# nandboard-pcb_rev_d.net
KiCad netlist of a schematic drawn in EAGLE
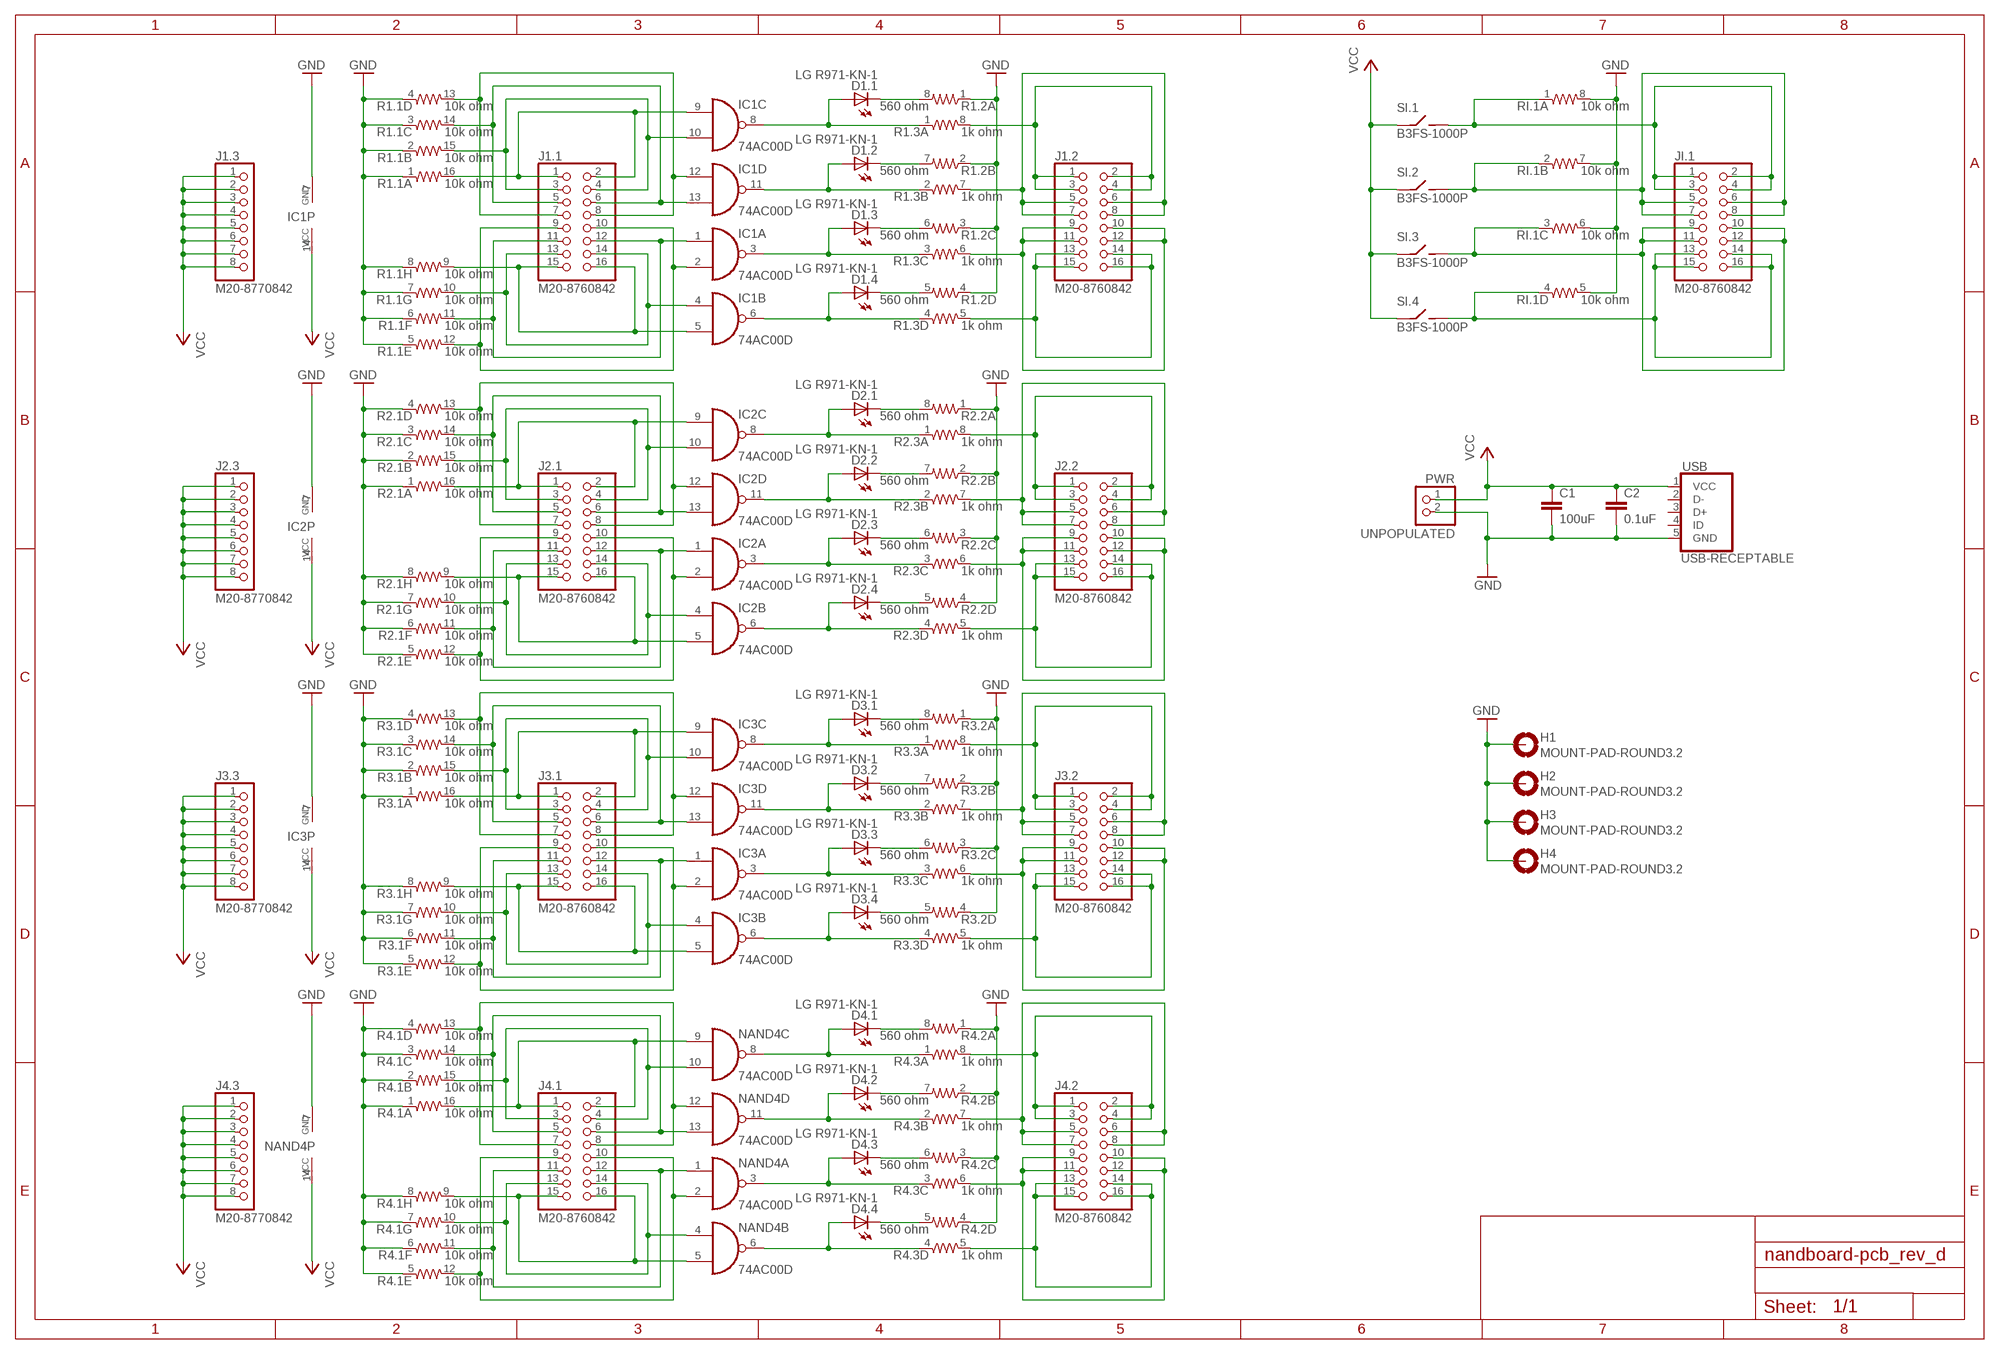
[diagram p0: schematic, sheet 1]

(export (version "E")
  (design (tool "Eeschema 10.0.6"))
  (components
    (comp (ref "C1")
      (value "100uF")
      (footprint "eagle-import:C1210")
      (libsource (lib "eagle-import") (part "C-EUC1210"))
    )
    (comp (ref "C2")
      (value "0.1uF")
      (footprint "eagle-import:C0805")
      (libsource (lib "eagle-import") (part "C-EUC0805"))
    )
    (comp (ref "D1.1")
      (value "LG R971-KN-1")
      (footprint "eagle-import:CHIPLED_0805")
      (libsource (lib "eagle-import") (part "LEDCHIPLED_0805"))
    )
    (comp (ref "D1.2")
      (value "LG R971-KN-1")
      (footprint "eagle-import:CHIPLED_0805")
      (libsource (lib "eagle-import") (part "LEDCHIPLED_0805"))
    )
    (comp (ref "D1.3")
      (value "LG R971-KN-1")
      (footprint "eagle-import:CHIPLED_0805")
      (libsource (lib "eagle-import") (part "LEDCHIPLED_0805"))
    )
    (comp (ref "D1.4")
      (value "LG R971-KN-1")
      (footprint "eagle-import:CHIPLED_0805")
      (libsource (lib "eagle-import") (part "LEDCHIPLED_0805"))
    )
    (comp (ref "D2.1")
      (value "LG R971-KN-1")
      (footprint "eagle-import:CHIPLED_0805")
      (libsource (lib "eagle-import") (part "LEDCHIPLED_0805"))
    )
    (comp (ref "D2.2")
      (value "LG R971-KN-1")
      (footprint "eagle-import:CHIPLED_0805")
      (libsource (lib "eagle-import") (part "LEDCHIPLED_0805"))
    )
    (comp (ref "D2.3")
      (value "LG R971-KN-1")
      (footprint "eagle-import:CHIPLED_0805")
      (libsource (lib "eagle-import") (part "LEDCHIPLED_0805"))
    )
    (comp (ref "D2.4")
      (value "LG R971-KN-1")
      (footprint "eagle-import:CHIPLED_0805")
      (libsource (lib "eagle-import") (part "LEDCHIPLED_0805"))
    )
    (comp (ref "D3.1")
      (value "LG R971-KN-1")
      (footprint "eagle-import:CHIPLED_0805")
      (libsource (lib "eagle-import") (part "LEDCHIPLED_0805"))
    )
    (comp (ref "D3.2")
      (value "LG R971-KN-1")
      (footprint "eagle-import:CHIPLED_0805")
      (libsource (lib "eagle-import") (part "LEDCHIPLED_0805"))
    )
    (comp (ref "D3.3")
      (value "LG R971-KN-1")
      (footprint "eagle-import:CHIPLED_0805")
      (libsource (lib "eagle-import") (part "LEDCHIPLED_0805"))
    )
    (comp (ref "D3.4")
      (value "LG R971-KN-1")
      (footprint "eagle-import:CHIPLED_0805")
      (libsource (lib "eagle-import") (part "LEDCHIPLED_0805"))
    )
    (comp (ref "D4.1")
      (value "LG R971-KN-1")
      (footprint "eagle-import:CHIPLED_0805")
      (libsource (lib "eagle-import") (part "LEDCHIPLED_0805"))
    )
    (comp (ref "D4.2")
      (value "LG R971-KN-1")
      (footprint "eagle-import:CHIPLED_0805")
      (libsource (lib "eagle-import") (part "LEDCHIPLED_0805"))
    )
    (comp (ref "D4.3")
      (value "LG R971-KN-1")
      (footprint "eagle-import:CHIPLED_0805")
      (libsource (lib "eagle-import") (part "LEDCHIPLED_0805"))
    )
    (comp (ref "D4.4")
      (value "LG R971-KN-1")
      (footprint "eagle-import:CHIPLED_0805")
      (libsource (lib "eagle-import") (part "LEDCHIPLED_0805"))
    )
    (comp (ref "H1")
      (value "MOUNT-PAD-ROUND3.2")
      (footprint "eagle-import:3,2-PAD")
      (libsource (lib "eagle-import") (part "MOUNT-PAD-ROUND3.2"))
    )
    (comp (ref "H2")
      (value "MOUNT-PAD-ROUND3.2")
      (footprint "eagle-import:3,2-PAD")
      (libsource (lib "eagle-import") (part "MOUNT-PAD-ROUND3.2"))
    )
    (comp (ref "H3")
      (value "MOUNT-PAD-ROUND3.2")
      (footprint "eagle-import:3,2-PAD")
      (libsource (lib "eagle-import") (part "MOUNT-PAD-ROUND3.2"))
    )
    (comp (ref "H4")
      (value "MOUNT-PAD-ROUND3.2")
      (footprint "eagle-import:3,2-PAD")
      (libsource (lib "eagle-import") (part "MOUNT-PAD-ROUND3.2"))
    )
    (comp (ref "IC1")
      (value "74AC00D")
      (footprint "eagle-import:SO14")
      (libsource (lib "eagle-import") (part "7400DAC"))
    )
    (comp (ref "IC2")
      (value "74AC00D")
      (footprint "eagle-import:SO14")
      (libsource (lib "eagle-import") (part "7400DAC"))
    )
    (comp (ref "IC3")
      (value "74AC00D")
      (footprint "eagle-import:SO14")
      (libsource (lib "eagle-import") (part "7400DAC"))
    )
    (comp (ref "J1.1")
      (value "M20-8760842")
      (footprint "eagle-import:2X08_SMT")
      (libsource (lib "eagle-import") (part "PINHD-2X8SMT"))
    )
    (comp (ref "J1.2")
      (value "M20-8760842")
      (footprint "eagle-import:2X08_SMT")
      (libsource (lib "eagle-import") (part "PINHD-2X8SMT"))
    )
    (comp (ref "J1.3")
      (value "M20-8770842")
      (footprint "eagle-import:1X08_SMT")
      (libsource (lib "eagle-import") (part "PINHD-1X81X08_SMT"))
    )
    (comp (ref "J2.1")
      (value "M20-8760842")
      (footprint "eagle-import:2X08_SMT")
      (libsource (lib "eagle-import") (part "PINHD-2X8SMT"))
    )
    (comp (ref "J2.2")
      (value "M20-8760842")
      (footprint "eagle-import:2X08_SMT")
      (libsource (lib "eagle-import") (part "PINHD-2X8SMT"))
    )
    (comp (ref "J2.3")
      (value "M20-8770842")
      (footprint "eagle-import:1X08_SMT")
      (libsource (lib "eagle-import") (part "PINHD-1X81X08_SMT"))
    )
    (comp (ref "J3.1")
      (value "M20-8760842")
      (footprint "eagle-import:2X08_SMT")
      (libsource (lib "eagle-import") (part "PINHD-2X8SMT"))
    )
    (comp (ref "J3.2")
      (value "M20-8760842")
      (footprint "eagle-import:2X08_SMT")
      (libsource (lib "eagle-import") (part "PINHD-2X8SMT"))
    )
    (comp (ref "J3.3")
      (value "M20-8770842")
      (footprint "eagle-import:1X08_SMT")
      (libsource (lib "eagle-import") (part "PINHD-1X81X08_SMT"))
    )
    (comp (ref "J4.1")
      (value "M20-8760842")
      (footprint "eagle-import:2X08_SMT")
      (libsource (lib "eagle-import") (part "PINHD-2X8SMT"))
    )
    (comp (ref "J4.2")
      (value "M20-8760842")
      (footprint "eagle-import:2X08_SMT")
      (libsource (lib "eagle-import") (part "PINHD-2X8SMT"))
    )
    (comp (ref "J4.3")
      (value "M20-8770842")
      (footprint "eagle-import:1X08_SMT")
      (libsource (lib "eagle-import") (part "PINHD-1X81X08_SMT"))
    )
    (comp (ref "JI.1")
      (value "M20-8760842")
      (footprint "eagle-import:2X08_SMT")
      (libsource (lib "eagle-import") (part "PINHD-2X8SMT"))
    )
    (comp (ref "NAND4")
      (value "74AC00D")
      (footprint "eagle-import:SO14")
      (libsource (lib "eagle-import") (part "7400DAC"))
    )
    (comp (ref "PWR")
      (value "UNPOPULATED")
      (footprint "eagle-import:1X02")
      (libsource (lib "eagle-import") (part "PINHD-1X2"))
    )
    (comp (ref "R1.1")
      (value "10k ohm")
      (footprint "eagle-import:742-16")
      (libsource (lib "eagle-import") (part "742-16_S"))
    )
    (comp (ref "R1.2")
      (value "560 ohm")
      (footprint "eagle-import:742-8")
      (libsource (lib "eagle-import") (part "742-8_S"))
    )
    (comp (ref "R1.3")
      (value "1k ohm")
      (footprint "eagle-import:742-8")
      (libsource (lib "eagle-import") (part "742-8_S"))
    )
    (comp (ref "R2.1")
      (value "10k ohm")
      (footprint "eagle-import:742-16")
      (libsource (lib "eagle-import") (part "742-16_S"))
    )
    (comp (ref "R2.2")
      (value "560 ohm")
      (footprint "eagle-import:742-8")
      (libsource (lib "eagle-import") (part "742-8_S"))
    )
    (comp (ref "R2.3")
      (value "1k ohm")
      (footprint "eagle-import:742-8")
      (libsource (lib "eagle-import") (part "742-8_S"))
    )
    (comp (ref "R3.1")
      (value "10k ohm")
      (footprint "eagle-import:742-16")
      (libsource (lib "eagle-import") (part "742-16_S"))
    )
    (comp (ref "R3.2")
      (value "560 ohm")
      (footprint "eagle-import:742-8")
      (libsource (lib "eagle-import") (part "742-8_S"))
    )
    (comp (ref "R3.3")
      (value "1k ohm")
      (footprint "eagle-import:742-8")
      (libsource (lib "eagle-import") (part "742-8_S"))
    )
    (comp (ref "R4.1")
      (value "10k ohm")
      (footprint "eagle-import:742-16")
      (libsource (lib "eagle-import") (part "742-16_S"))
    )
    (comp (ref "R4.2")
      (value "560 ohm")
      (footprint "eagle-import:742-8")
      (libsource (lib "eagle-import") (part "742-8_S"))
    )
    (comp (ref "R4.3")
      (value "1k ohm")
      (footprint "eagle-import:742-8")
      (libsource (lib "eagle-import") (part "742-8_S"))
    )
    (comp (ref "RI.1")
      (value "10k ohm")
      (footprint "eagle-import:742-8")
      (libsource (lib "eagle-import") (part "742-8_S"))
    )
    (comp (ref "SI.1")
      (value "B3FS-1000P")
      (footprint "eagle-import:B3FS-1000")
      (libsource (lib "eagle-import") (part "SPSTB3FS-1000"))
    )
    (comp (ref "SI.2")
      (value "B3FS-1000P")
      (footprint "eagle-import:B3FS-1000")
      (libsource (lib "eagle-import") (part "SPSTB3FS-1000"))
    )
    (comp (ref "SI.3")
      (value "B3FS-1000P")
      (footprint "eagle-import:B3FS-1000")
      (libsource (lib "eagle-import") (part "SPSTB3FS-1000"))
    )
    (comp (ref "SI.4")
      (value "B3FS-1000P")
      (footprint "eagle-import:B3FS-1000")
      (libsource (lib "eagle-import") (part "SPSTB3FS-1000"))
    )
    (comp (ref "USB")
      (value "USB-RECEPTABLE")
      (footprint "eagle-import:FCI-10103594-0001LF")
      (libsource (lib "eagle-import") (part "USB-RECEPTABLE"))
    )
  )
  (nets
    (net (code "1") (name "GND") (class "Default")
      (node (ref "C1") (pin "2") (pinfunction "2_2") (pintype "passive"))
      (node (ref "C2") (pin "2") (pinfunction "2_2") (pintype "passive"))
      (node (ref "H1") (pin "B3,2") (pinfunction "MOUNT_B3,2") (pintype "passive"))
      (node (ref "H2") (pin "B3,2") (pinfunction "MOUNT_B3,2") (pintype "passive"))
      (node (ref "H3") (pin "B3,2") (pinfunction "MOUNT_B3,2") (pintype "passive"))
      (node (ref "H4") (pin "B3,2") (pinfunction "MOUNT_B3,2") (pintype "passive"))
      (node (ref "IC1") (pin "7") (pinfunction "GND_7") (pintype "power_in"))
      (node (ref "IC2") (pin "7") (pinfunction "GND_7") (pintype "power_in"))
      (node (ref "IC3") (pin "7") (pinfunction "GND_7") (pintype "power_in"))
      (node (ref "NAND4") (pin "7") (pinfunction "GND_7") (pintype "power_in"))
      (node (ref "PWR") (pin "2") (pinfunction "2_2") (pintype "passive"))
      (node (ref "R1.1") (pin "1") (pinfunction "1_1") (pintype "passive"))
      (node (ref "R1.1") (pin "2") (pinfunction "1_2") (pintype "passive"))
      (node (ref "R1.1") (pin "3") (pinfunction "1_3") (pintype "passive"))
      (node (ref "R1.1") (pin "4") (pinfunction "1_4") (pintype "passive"))
      (node (ref "R1.1") (pin "5") (pinfunction "1_5") (pintype "passive"))
      (node (ref "R1.1") (pin "6") (pinfunction "1_6") (pintype "passive"))
      (node (ref "R1.1") (pin "7") (pinfunction "1_7") (pintype "passive"))
      (node (ref "R1.1") (pin "8") (pinfunction "1_8") (pintype "passive"))
      (node (ref "R1.2") (pin "1") (pinfunction "1_1") (pintype "passive"))
      (node (ref "R1.2") (pin "2") (pinfunction "1_2") (pintype "passive"))
      (node (ref "R1.2") (pin "3") (pinfunction "1_3") (pintype "passive"))
      (node (ref "R1.2") (pin "4") (pinfunction "1_4") (pintype "passive"))
      (node (ref "R2.1") (pin "1") (pinfunction "1_1") (pintype "passive"))
      (node (ref "R2.1") (pin "2") (pinfunction "1_2") (pintype "passive"))
      (node (ref "R2.1") (pin "3") (pinfunction "1_3") (pintype "passive"))
      (node (ref "R2.1") (pin "4") (pinfunction "1_4") (pintype "passive"))
      (node (ref "R2.1") (pin "5") (pinfunction "1_5") (pintype "passive"))
      (node (ref "R2.1") (pin "6") (pinfunction "1_6") (pintype "passive"))
      (node (ref "R2.1") (pin "7") (pinfunction "1_7") (pintype "passive"))
      (node (ref "R2.1") (pin "8") (pinfunction "1_8") (pintype "passive"))
      (node (ref "R2.2") (pin "1") (pinfunction "1_1") (pintype "passive"))
      (node (ref "R2.2") (pin "2") (pinfunction "1_2") (pintype "passive"))
      (node (ref "R2.2") (pin "3") (pinfunction "1_3") (pintype "passive"))
      (node (ref "R2.2") (pin "4") (pinfunction "1_4") (pintype "passive"))
      (node (ref "R3.1") (pin "1") (pinfunction "1_1") (pintype "passive"))
      (node (ref "R3.1") (pin "2") (pinfunction "1_2") (pintype "passive"))
      (node (ref "R3.1") (pin "3") (pinfunction "1_3") (pintype "passive"))
      (node (ref "R3.1") (pin "4") (pinfunction "1_4") (pintype "passive"))
      (node (ref "R3.1") (pin "5") (pinfunction "1_5") (pintype "passive"))
      (node (ref "R3.1") (pin "6") (pinfunction "1_6") (pintype "passive"))
      (node (ref "R3.1") (pin "7") (pinfunction "1_7") (pintype "passive"))
      (node (ref "R3.1") (pin "8") (pinfunction "1_8") (pintype "passive"))
      (node (ref "R3.2") (pin "1") (pinfunction "1_1") (pintype "passive"))
      (node (ref "R3.2") (pin "2") (pinfunction "1_2") (pintype "passive"))
      (node (ref "R3.2") (pin "3") (pinfunction "1_3") (pintype "passive"))
      (node (ref "R3.2") (pin "4") (pinfunction "1_4") (pintype "passive"))
      (node (ref "R4.1") (pin "1") (pinfunction "1_1") (pintype "passive"))
      (node (ref "R4.1") (pin "2") (pinfunction "1_2") (pintype "passive"))
      (node (ref "R4.1") (pin "3") (pinfunction "1_3") (pintype "passive"))
      (node (ref "R4.1") (pin "4") (pinfunction "1_4") (pintype "passive"))
      (node (ref "R4.1") (pin "5") (pinfunction "1_5") (pintype "passive"))
      (node (ref "R4.1") (pin "6") (pinfunction "1_6") (pintype "passive"))
      (node (ref "R4.1") (pin "7") (pinfunction "1_7") (pintype "passive"))
      (node (ref "R4.1") (pin "8") (pinfunction "1_8") (pintype "passive"))
      (node (ref "R4.2") (pin "1") (pinfunction "1_1") (pintype "passive"))
      (node (ref "R4.2") (pin "2") (pinfunction "1_2") (pintype "passive"))
      (node (ref "R4.2") (pin "3") (pinfunction "1_3") (pintype "passive"))
      (node (ref "R4.2") (pin "4") (pinfunction "1_4") (pintype "passive"))
      (node (ref "RI.1") (pin "5") (pinfunction "2_5") (pintype "passive"))
      (node (ref "RI.1") (pin "6") (pinfunction "2_6") (pintype "passive"))
      (node (ref "RI.1") (pin "7") (pinfunction "2_7") (pintype "passive"))
      (node (ref "RI.1") (pin "8") (pinfunction "2_8") (pintype "passive"))
      (node (ref "USB") (pin "5") (pinfunction "GND_5") (pintype "bidirectional"))
    )
    (net (code "2") (name "Net-(IC1A-I0)") (class "Default")
      (node (ref "IC1") (pin "1") (pinfunction "I0_1") (pintype "input"))
      (node (ref "J1.1") (pin "11") (pinfunction "11_11") (pintype "passive"))
      (node (ref "J1.1") (pin "12") (pinfunction "12_12") (pintype "passive"))
      (node (ref "R1.1") (pin "11") (pinfunction "2_11") (pintype "passive"))
    )
    (net (code "3") (name "Net-(IC1A-I1)") (class "Default")
      (node (ref "IC1") (pin "2") (pinfunction "I1_2") (pintype "input"))
      (node (ref "J1.1") (pin "10") (pinfunction "10_10") (pintype "passive"))
      (node (ref "J1.1") (pin "9") (pinfunction "9_9") (pintype "passive"))
      (node (ref "R1.1") (pin "12") (pinfunction "2_12") (pintype "passive"))
    )
    (net (code "4") (name "Net-(IC1A-O)") (class "Default")
      (node (ref "D1.3") (pin "A") (pinfunction "A_A") (pintype "passive"))
      (node (ref "IC1") (pin "3") (pinfunction "O_3") (pintype "output"))
      (node (ref "R1.3") (pin "3") (pinfunction "1_3") (pintype "passive"))
    )
    (net (code "5") (name "Net-(IC1B-I0)") (class "Default")
      (node (ref "IC1") (pin "4") (pinfunction "I0_4") (pintype "input"))
      (node (ref "J1.1") (pin "13") (pinfunction "13_13") (pintype "passive"))
      (node (ref "J1.1") (pin "14") (pinfunction "14_14") (pintype "passive"))
      (node (ref "R1.1") (pin "10") (pinfunction "2_10") (pintype "passive"))
    )
    (net (code "6") (name "Net-(IC1B-I1)") (class "Default")
      (node (ref "IC1") (pin "5") (pinfunction "I1_5") (pintype "input"))
      (node (ref "J1.1") (pin "15") (pinfunction "15_15") (pintype "passive"))
      (node (ref "J1.1") (pin "16") (pinfunction "16_16") (pintype "passive"))
      (node (ref "R1.1") (pin "9") (pinfunction "2_9") (pintype "passive"))
    )
    (net (code "7") (name "Net-(IC1B-O)") (class "Default")
      (node (ref "D1.4") (pin "A") (pinfunction "A_A") (pintype "passive"))
      (node (ref "IC1") (pin "6") (pinfunction "O_6") (pintype "output"))
      (node (ref "R1.3") (pin "4") (pinfunction "1_4") (pintype "passive"))
    )
    (net (code "8") (name "Net-(IC1C-I0)") (class "Default")
      (node (ref "IC1") (pin "9") (pinfunction "I0_9") (pintype "input"))
      (node (ref "J1.1") (pin "1") (pinfunction "1_1") (pintype "passive"))
      (node (ref "J1.1") (pin "2") (pinfunction "2_2") (pintype "passive"))
      (node (ref "R1.1") (pin "16") (pinfunction "2_16") (pintype "passive"))
    )
    (net (code "9") (name "Net-(IC1C-I1)") (class "Default")
      (node (ref "IC1") (pin "10") (pinfunction "I1_10") (pintype "input"))
      (node (ref "J1.1") (pin "3") (pinfunction "3_3") (pintype "passive"))
      (node (ref "J1.1") (pin "4") (pinfunction "4_4") (pintype "passive"))
      (node (ref "R1.1") (pin "15") (pinfunction "2_15") (pintype "passive"))
    )
    (net (code "10") (name "Net-(IC1C-O)") (class "Default")
      (node (ref "D1.1") (pin "A") (pinfunction "A_A") (pintype "passive"))
      (node (ref "IC1") (pin "8") (pinfunction "O_8") (pintype "output"))
      (node (ref "R1.3") (pin "1") (pinfunction "1_1") (pintype "passive"))
    )
    (net (code "11") (name "Net-(IC1D-I0)") (class "Default")
      (node (ref "IC1") (pin "12") (pinfunction "I0_12") (pintype "input"))
      (node (ref "J1.1") (pin "7") (pinfunction "7_7") (pintype "passive"))
      (node (ref "J1.1") (pin "8") (pinfunction "8_8") (pintype "passive"))
      (node (ref "R1.1") (pin "13") (pinfunction "2_13") (pintype "passive"))
    )
    (net (code "12") (name "Net-(IC1D-I1)") (class "Default")
      (node (ref "IC1") (pin "13") (pinfunction "I1_13") (pintype "input"))
      (node (ref "J1.1") (pin "5") (pinfunction "5_5") (pintype "passive"))
      (node (ref "J1.1") (pin "6") (pinfunction "6_6") (pintype "passive"))
      (node (ref "R1.1") (pin "14") (pinfunction "2_14") (pintype "passive"))
    )
    (net (code "13") (name "Net-(IC1D-O)") (class "Default")
      (node (ref "D1.2") (pin "A") (pinfunction "A_A") (pintype "passive"))
      (node (ref "IC1") (pin "11") (pinfunction "O_11") (pintype "output"))
      (node (ref "R1.3") (pin "2") (pinfunction "1_2") (pintype "passive"))
    )
    (net (code "14") (name "Net-(IC2A-I0)") (class "Default")
      (node (ref "IC2") (pin "1") (pinfunction "I0_1") (pintype "input"))
      (node (ref "J2.1") (pin "11") (pinfunction "11_11") (pintype "passive"))
      (node (ref "J2.1") (pin "12") (pinfunction "12_12") (pintype "passive"))
      (node (ref "R2.1") (pin "11") (pinfunction "2_11") (pintype "passive"))
    )
    (net (code "15") (name "Net-(IC2A-I1)") (class "Default")
      (node (ref "IC2") (pin "2") (pinfunction "I1_2") (pintype "input"))
      (node (ref "J2.1") (pin "10") (pinfunction "10_10") (pintype "passive"))
      (node (ref "J2.1") (pin "9") (pinfunction "9_9") (pintype "passive"))
      (node (ref "R2.1") (pin "12") (pinfunction "2_12") (pintype "passive"))
    )
    (net (code "16") (name "Net-(IC2A-O)") (class "Default")
      (node (ref "D2.3") (pin "A") (pinfunction "A_A") (pintype "passive"))
      (node (ref "IC2") (pin "3") (pinfunction "O_3") (pintype "output"))
      (node (ref "R2.3") (pin "3") (pinfunction "1_3") (pintype "passive"))
    )
    (net (code "17") (name "Net-(IC2B-I0)") (class "Default")
      (node (ref "IC2") (pin "4") (pinfunction "I0_4") (pintype "input"))
      (node (ref "J2.1") (pin "13") (pinfunction "13_13") (pintype "passive"))
      (node (ref "J2.1") (pin "14") (pinfunction "14_14") (pintype "passive"))
      (node (ref "R2.1") (pin "10") (pinfunction "2_10") (pintype "passive"))
    )
    (net (code "18") (name "Net-(IC2B-I1)") (class "Default")
      (node (ref "IC2") (pin "5") (pinfunction "I1_5") (pintype "input"))
      (node (ref "J2.1") (pin "15") (pinfunction "15_15") (pintype "passive"))
      (node (ref "J2.1") (pin "16") (pinfunction "16_16") (pintype "passive"))
      (node (ref "R2.1") (pin "9") (pinfunction "2_9") (pintype "passive"))
    )
    (net (code "19") (name "Net-(IC2B-O)") (class "Default")
      (node (ref "D2.4") (pin "A") (pinfunction "A_A") (pintype "passive"))
      (node (ref "IC2") (pin "6") (pinfunction "O_6") (pintype "output"))
      (node (ref "R2.3") (pin "4") (pinfunction "1_4") (pintype "passive"))
    )
    (net (code "20") (name "Net-(IC2C-I0)") (class "Default")
      (node (ref "IC2") (pin "9") (pinfunction "I0_9") (pintype "input"))
      (node (ref "J2.1") (pin "1") (pinfunction "1_1") (pintype "passive"))
      (node (ref "J2.1") (pin "2") (pinfunction "2_2") (pintype "passive"))
      (node (ref "R2.1") (pin "16") (pinfunction "2_16") (pintype "passive"))
    )
    (net (code "21") (name "Net-(IC2C-I1)") (class "Default")
      (node (ref "IC2") (pin "10") (pinfunction "I1_10") (pintype "input"))
      (node (ref "J2.1") (pin "3") (pinfunction "3_3") (pintype "passive"))
      (node (ref "J2.1") (pin "4") (pinfunction "4_4") (pintype "passive"))
      (node (ref "R2.1") (pin "15") (pinfunction "2_15") (pintype "passive"))
    )
    (net (code "22") (name "Net-(IC2C-O)") (class "Default")
      (node (ref "D2.1") (pin "A") (pinfunction "A_A") (pintype "passive"))
      (node (ref "IC2") (pin "8") (pinfunction "O_8") (pintype "output"))
      (node (ref "R2.3") (pin "1") (pinfunction "1_1") (pintype "passive"))
    )
    (net (code "23") (name "Net-(IC2D-I0)") (class "Default")
      (node (ref "IC2") (pin "12") (pinfunction "I0_12") (pintype "input"))
      (node (ref "J2.1") (pin "7") (pinfunction "7_7") (pintype "passive"))
      (node (ref "J2.1") (pin "8") (pinfunction "8_8") (pintype "passive"))
      (node (ref "R2.1") (pin "13") (pinfunction "2_13") (pintype "passive"))
    )
    (net (code "24") (name "Net-(IC2D-I1)") (class "Default")
      (node (ref "IC2") (pin "13") (pinfunction "I1_13") (pintype "input"))
      (node (ref "J2.1") (pin "5") (pinfunction "5_5") (pintype "passive"))
      (node (ref "J2.1") (pin "6") (pinfunction "6_6") (pintype "passive"))
      (node (ref "R2.1") (pin "14") (pinfunction "2_14") (pintype "passive"))
    )
    (net (code "25") (name "Net-(IC2D-O)") (class "Default")
      (node (ref "D2.2") (pin "A") (pinfunction "A_A") (pintype "passive"))
      (node (ref "IC2") (pin "11") (pinfunction "O_11") (pintype "output"))
      (node (ref "R2.3") (pin "2") (pinfunction "1_2") (pintype "passive"))
    )
    (net (code "26") (name "Net-(IC3A-I0)") (class "Default")
      (node (ref "IC3") (pin "1") (pinfunction "I0_1") (pintype "input"))
      (node (ref "J3.1") (pin "11") (pinfunction "11_11") (pintype "passive"))
      (node (ref "J3.1") (pin "12") (pinfunction "12_12") (pintype "passive"))
      (node (ref "R3.1") (pin "11") (pinfunction "2_11") (pintype "passive"))
    )
    (net (code "27") (name "Net-(IC3A-I1)") (class "Default")
      (node (ref "IC3") (pin "2") (pinfunction "I1_2") (pintype "input"))
      (node (ref "J3.1") (pin "10") (pinfunction "10_10") (pintype "passive"))
      (node (ref "J3.1") (pin "9") (pinfunction "9_9") (pintype "passive"))
      (node (ref "R3.1") (pin "12") (pinfunction "2_12") (pintype "passive"))
    )
    (net (code "28") (name "Net-(IC3A-O)") (class "Default")
      (node (ref "D3.3") (pin "A") (pinfunction "A_A") (pintype "passive"))
      (node (ref "IC3") (pin "3") (pinfunction "O_3") (pintype "output"))
      (node (ref "R3.3") (pin "3") (pinfunction "1_3") (pintype "passive"))
    )
    (net (code "29") (name "Net-(IC3B-I0)") (class "Default")
      (node (ref "IC3") (pin "4") (pinfunction "I0_4") (pintype "input"))
      (node (ref "J3.1") (pin "13") (pinfunction "13_13") (pintype "passive"))
      (node (ref "J3.1") (pin "14") (pinfunction "14_14") (pintype "passive"))
      (node (ref "R3.1") (pin "10") (pinfunction "2_10") (pintype "passive"))
    )
    (net (code "30") (name "Net-(IC3B-I1)") (class "Default")
      (node (ref "IC3") (pin "5") (pinfunction "I1_5") (pintype "input"))
      (node (ref "J3.1") (pin "15") (pinfunction "15_15") (pintype "passive"))
      (node (ref "J3.1") (pin "16") (pinfunction "16_16") (pintype "passive"))
      (node (ref "R3.1") (pin "9") (pinfunction "2_9") (pintype "passive"))
    )
    (net (code "31") (name "Net-(IC3B-O)") (class "Default")
      (node (ref "D3.4") (pin "A") (pinfunction "A_A") (pintype "passive"))
      (node (ref "IC3") (pin "6") (pinfunction "O_6") (pintype "output"))
      (node (ref "R3.3") (pin "4") (pinfunction "1_4") (pintype "passive"))
    )
    (net (code "32") (name "Net-(IC3C-I0)") (class "Default")
      (node (ref "IC3") (pin "9") (pinfunction "I0_9") (pintype "input"))
      (node (ref "J3.1") (pin "1") (pinfunction "1_1") (pintype "passive"))
      (node (ref "J3.1") (pin "2") (pinfunction "2_2") (pintype "passive"))
      (node (ref "R3.1") (pin "16") (pinfunction "2_16") (pintype "passive"))
    )
    (net (code "33") (name "Net-(IC3C-I1)") (class "Default")
      (node (ref "IC3") (pin "10") (pinfunction "I1_10") (pintype "input"))
      (node (ref "J3.1") (pin "3") (pinfunction "3_3") (pintype "passive"))
      (node (ref "J3.1") (pin "4") (pinfunction "4_4") (pintype "passive"))
      (node (ref "R3.1") (pin "15") (pinfunction "2_15") (pintype "passive"))
    )
    (net (code "34") (name "Net-(IC3C-O)") (class "Default")
      (node (ref "D3.1") (pin "A") (pinfunction "A_A") (pintype "passive"))
      (node (ref "IC3") (pin "8") (pinfunction "O_8") (pintype "output"))
      (node (ref "R3.3") (pin "1") (pinfunction "1_1") (pintype "passive"))
    )
    (net (code "35") (name "Net-(IC3D-I0)") (class "Default")
      (node (ref "IC3") (pin "12") (pinfunction "I0_12") (pintype "input"))
      (node (ref "J3.1") (pin "7") (pinfunction "7_7") (pintype "passive"))
      (node (ref "J3.1") (pin "8") (pinfunction "8_8") (pintype "passive"))
      (node (ref "R3.1") (pin "13") (pinfunction "2_13") (pintype "passive"))
    )
    (net (code "36") (name "Net-(IC3D-I1)") (class "Default")
      (node (ref "IC3") (pin "13") (pinfunction "I1_13") (pintype "input"))
      (node (ref "J3.1") (pin "5") (pinfunction "5_5") (pintype "passive"))
      (node (ref "J3.1") (pin "6") (pinfunction "6_6") (pintype "passive"))
      (node (ref "R3.1") (pin "14") (pinfunction "2_14") (pintype "passive"))
    )
    (net (code "37") (name "Net-(IC3D-O)") (class "Default")
      (node (ref "D3.2") (pin "A") (pinfunction "A_A") (pintype "passive"))
      (node (ref "IC3") (pin "11") (pinfunction "O_11") (pintype "output"))
      (node (ref "R3.3") (pin "2") (pinfunction "1_2") (pintype "passive"))
    )
    (net (code "38") (name "Net-(JI.1-Pad1)") (class "Default")
      (node (ref "JI.1") (pin "1") (pinfunction "1_1") (pintype "passive"))
      (node (ref "JI.1") (pin "2") (pinfunction "2_2") (pintype "passive"))
      (node (ref "JI.1") (pin "3") (pinfunction "3_3") (pintype "passive"))
      (node (ref "JI.1") (pin "4") (pinfunction "4_4") (pintype "passive"))
      (node (ref "RI.1") (pin "1") (pinfunction "1_1") (pintype "passive"))
      (node (ref "SI.1") (pin "3") (pinfunction "B_3") (pintype "bidirectional"))
      (node (ref "SI.1") (pin "4") (pinfunction "B_4") (pintype "bidirectional"))
    )
    (net (code "39") (name "Net-(NAND4A-I0)") (class "Default")
      (node (ref "J4.1") (pin "11") (pinfunction "11_11") (pintype "passive"))
      (node (ref "J4.1") (pin "12") (pinfunction "12_12") (pintype "passive"))
      (node (ref "NAND4") (pin "1") (pinfunction "I0_1") (pintype "input"))
      (node (ref "R4.1") (pin "11") (pinfunction "2_11") (pintype "passive"))
    )
    (net (code "40") (name "Net-(NAND4A-I1)") (class "Default")
      (node (ref "J4.1") (pin "10") (pinfunction "10_10") (pintype "passive"))
      (node (ref "J4.1") (pin "9") (pinfunction "9_9") (pintype "passive"))
      (node (ref "NAND4") (pin "2") (pinfunction "I1_2") (pintype "input"))
      (node (ref "R4.1") (pin "12") (pinfunction "2_12") (pintype "passive"))
    )
    (net (code "41") (name "Net-(NAND4A-O)") (class "Default")
      (node (ref "D4.3") (pin "A") (pinfunction "A_A") (pintype "passive"))
      (node (ref "NAND4") (pin "3") (pinfunction "O_3") (pintype "output"))
      (node (ref "R4.3") (pin "3") (pinfunction "1_3") (pintype "passive"))
    )
    (net (code "42") (name "Net-(NAND4B-I0)") (class "Default")
      (node (ref "J4.1") (pin "13") (pinfunction "13_13") (pintype "passive"))
      (node (ref "J4.1") (pin "14") (pinfunction "14_14") (pintype "passive"))
      (node (ref "NAND4") (pin "4") (pinfunction "I0_4") (pintype "input"))
      (node (ref "R4.1") (pin "10") (pinfunction "2_10") (pintype "passive"))
    )
    (net (code "43") (name "Net-(NAND4B-I1)") (class "Default")
      (node (ref "J4.1") (pin "15") (pinfunction "15_15") (pintype "passive"))
      (node (ref "J4.1") (pin "16") (pinfunction "16_16") (pintype "passive"))
      (node (ref "NAND4") (pin "5") (pinfunction "I1_5") (pintype "input"))
      (node (ref "R4.1") (pin "9") (pinfunction "2_9") (pintype "passive"))
    )
    (net (code "44") (name "Net-(NAND4B-O)") (class "Default")
      (node (ref "D4.4") (pin "A") (pinfunction "A_A") (pintype "passive"))
      (node (ref "NAND4") (pin "6") (pinfunction "O_6") (pintype "output"))
      (node (ref "R4.3") (pin "4") (pinfunction "1_4") (pintype "passive"))
    )
    (net (code "45") (name "Net-(NAND4C-I0)") (class "Default")
      (node (ref "J4.1") (pin "1") (pinfunction "1_1") (pintype "passive"))
      (node (ref "J4.1") (pin "2") (pinfunction "2_2") (pintype "passive"))
      (node (ref "NAND4") (pin "9") (pinfunction "I0_9") (pintype "input"))
      (node (ref "R4.1") (pin "16") (pinfunction "2_16") (pintype "passive"))
    )
    (net (code "46") (name "Net-(NAND4C-I1)") (class "Default")
      (node (ref "J4.1") (pin "3") (pinfunction "3_3") (pintype "passive"))
      (node (ref "J4.1") (pin "4") (pinfunction "4_4") (pintype "passive"))
      (node (ref "NAND4") (pin "10") (pinfunction "I1_10") (pintype "input"))
      (node (ref "R4.1") (pin "15") (pinfunction "2_15") (pintype "passive"))
    )
    (net (code "47") (name "Net-(NAND4C-O)") (class "Default")
      (node (ref "D4.1") (pin "A") (pinfunction "A_A") (pintype "passive"))
      (node (ref "NAND4") (pin "8") (pinfunction "O_8") (pintype "output"))
      (node (ref "R4.3") (pin "1") (pinfunction "1_1") (pintype "passive"))
    )
    (net (code "48") (name "Net-(NAND4D-I0)") (class "Default")
      (node (ref "J4.1") (pin "7") (pinfunction "7_7") (pintype "passive"))
      (node (ref "J4.1") (pin "8") (pinfunction "8_8") (pintype "passive"))
      (node (ref "NAND4") (pin "12") (pinfunction "I0_12") (pintype "input"))
      (node (ref "R4.1") (pin "13") (pinfunction "2_13") (pintype "passive"))
    )
    (net (code "49") (name "Net-(NAND4D-I1)") (class "Default")
      (node (ref "J4.1") (pin "5") (pinfunction "5_5") (pintype "passive"))
      (node (ref "J4.1") (pin "6") (pinfunction "6_6") (pintype "passive"))
      (node (ref "NAND4") (pin "13") (pinfunction "I1_13") (pintype "input"))
      (node (ref "R4.1") (pin "14") (pinfunction "2_14") (pintype "passive"))
    )
    (net (code "50") (name "Net-(NAND4D-O)") (class "Default")
      (node (ref "D4.2") (pin "A") (pinfunction "A_A") (pintype "passive"))
      (node (ref "NAND4") (pin "11") (pinfunction "O_11") (pintype "output"))
      (node (ref "R4.3") (pin "2") (pinfunction "1_2") (pintype "passive"))
    )
    (net (code "51") (name "Net-(R1.2A-2)") (class "Default")
      (node (ref "D1.1") (pin "C") (pinfunction "C_C") (pintype "passive"))
      (node (ref "R1.2") (pin "8") (pinfunction "2_8") (pintype "passive"))
    )
    (net (code "52") (name "Net-(R1.2B-2)") (class "Default")
      (node (ref "D1.2") (pin "C") (pinfunction "C_C") (pintype "passive"))
      (node (ref "R1.2") (pin "7") (pinfunction "2_7") (pintype "passive"))
    )
    (net (code "53") (name "Net-(R1.2C-2)") (class "Default")
      (node (ref "D1.3") (pin "C") (pinfunction "C_C") (pintype "passive"))
      (node (ref "R1.2") (pin "6") (pinfunction "2_6") (pintype "passive"))
    )
    (net (code "54") (name "Net-(R1.2D-2)") (class "Default")
      (node (ref "D1.4") (pin "C") (pinfunction "C_C") (pintype "passive"))
      (node (ref "R1.2") (pin "5") (pinfunction "2_5") (pintype "passive"))
    )
    (net (code "55") (name "Net-(R1.3A-2)") (class "Default")
      (node (ref "J1.2") (pin "1") (pinfunction "1_1") (pintype "passive"))
      (node (ref "J1.2") (pin "2") (pinfunction "2_2") (pintype "passive"))
      (node (ref "J1.2") (pin "3") (pinfunction "3_3") (pintype "passive"))
      (node (ref "J1.2") (pin "4") (pinfunction "4_4") (pintype "passive"))
      (node (ref "R1.3") (pin "8") (pinfunction "2_8") (pintype "passive"))
    )
    (net (code "56") (name "Net-(R1.3B-2)") (class "Default")
      (node (ref "J1.2") (pin "5") (pinfunction "5_5") (pintype "passive"))
      (node (ref "J1.2") (pin "6") (pinfunction "6_6") (pintype "passive"))
      (node (ref "J1.2") (pin "7") (pinfunction "7_7") (pintype "passive"))
      (node (ref "J1.2") (pin "8") (pinfunction "8_8") (pintype "passive"))
      (node (ref "R1.3") (pin "7") (pinfunction "2_7") (pintype "passive"))
    )
    (net (code "57") (name "Net-(R1.3C-2)") (class "Default")
      (node (ref "J1.2") (pin "10") (pinfunction "10_10") (pintype "passive"))
      (node (ref "J1.2") (pin "11") (pinfunction "11_11") (pintype "passive"))
      (node (ref "J1.2") (pin "12") (pinfunction "12_12") (pintype "passive"))
      (node (ref "J1.2") (pin "9") (pinfunction "9_9") (pintype "passive"))
      (node (ref "R1.3") (pin "6") (pinfunction "2_6") (pintype "passive"))
    )
    (net (code "58") (name "Net-(R1.3D-2)") (class "Default")
      (node (ref "J1.2") (pin "13") (pinfunction "13_13") (pintype "passive"))
      (node (ref "J1.2") (pin "14") (pinfunction "14_14") (pintype "passive"))
      (node (ref "J1.2") (pin "15") (pinfunction "15_15") (pintype "passive"))
      (node (ref "J1.2") (pin "16") (pinfunction "16_16") (pintype "passive"))
      (node (ref "R1.3") (pin "5") (pinfunction "2_5") (pintype "passive"))
    )
    (net (code "59") (name "Net-(R2.2A-2)") (class "Default")
      (node (ref "D2.1") (pin "C") (pinfunction "C_C") (pintype "passive"))
      (node (ref "R2.2") (pin "8") (pinfunction "2_8") (pintype "passive"))
    )
    (net (code "60") (name "Net-(R2.2B-2)") (class "Default")
      (node (ref "D2.2") (pin "C") (pinfunction "C_C") (pintype "passive"))
      (node (ref "R2.2") (pin "7") (pinfunction "2_7") (pintype "passive"))
    )
    (net (code "61") (name "Net-(R2.2C-2)") (class "Default")
      (node (ref "D2.3") (pin "C") (pinfunction "C_C") (pintype "passive"))
      (node (ref "R2.2") (pin "6") (pinfunction "2_6") (pintype "passive"))
    )
    (net (code "62") (name "Net-(R2.2D-2)") (class "Default")
      (node (ref "D2.4") (pin "C") (pinfunction "C_C") (pintype "passive"))
      (node (ref "R2.2") (pin "5") (pinfunction "2_5") (pintype "passive"))
    )
    (net (code "63") (name "Net-(R2.3A-2)") (class "Default")
      (node (ref "J2.2") (pin "1") (pinfunction "1_1") (pintype "passive"))
      (node (ref "J2.2") (pin "2") (pinfunction "2_2") (pintype "passive"))
      (node (ref "J2.2") (pin "3") (pinfunction "3_3") (pintype "passive"))
      (node (ref "J2.2") (pin "4") (pinfunction "4_4") (pintype "passive"))
      (node (ref "R2.3") (pin "8") (pinfunction "2_8") (pintype "passive"))
    )
    (net (code "64") (name "Net-(R2.3B-2)") (class "Default")
      (node (ref "J2.2") (pin "5") (pinfunction "5_5") (pintype "passive"))
      (node (ref "J2.2") (pin "6") (pinfunction "6_6") (pintype "passive"))
      (node (ref "J2.2") (pin "7") (pinfunction "7_7") (pintype "passive"))
      (node (ref "J2.2") (pin "8") (pinfunction "8_8") (pintype "passive"))
      (node (ref "R2.3") (pin "7") (pinfunction "2_7") (pintype "passive"))
    )
    (net (code "65") (name "Net-(R2.3C-2)") (class "Default")
      (node (ref "J2.2") (pin "10") (pinfunction "10_10") (pintype "passive"))
      (node (ref "J2.2") (pin "11") (pinfunction "11_11") (pintype "passive"))
      (node (ref "J2.2") (pin "12") (pinfunction "12_12") (pintype "passive"))
      (node (ref "J2.2") (pin "9") (pinfunction "9_9") (pintype "passive"))
      (node (ref "R2.3") (pin "6") (pinfunction "2_6") (pintype "passive"))
    )
    (net (code "66") (name "Net-(R2.3D-2)") (class "Default")
      (node (ref "J2.2") (pin "13") (pinfunction "13_13") (pintype "passive"))
      (node (ref "J2.2") (pin "14") (pinfunction "14_14") (pintype "passive"))
      (node (ref "J2.2") (pin "15") (pinfunction "15_15") (pintype "passive"))
      (node (ref "J2.2") (pin "16") (pinfunction "16_16") (pintype "passive"))
      (node (ref "R2.3") (pin "5") (pinfunction "2_5") (pintype "passive"))
    )
    (net (code "67") (name "Net-(R3.2A-2)") (class "Default")
      (node (ref "D3.1") (pin "C") (pinfunction "C_C") (pintype "passive"))
      (node (ref "R3.2") (pin "8") (pinfunction "2_8") (pintype "passive"))
    )
    (net (code "68") (name "Net-(R3.2B-2)") (class "Default")
      (node (ref "D3.2") (pin "C") (pinfunction "C_C") (pintype "passive"))
      (node (ref "R3.2") (pin "7") (pinfunction "2_7") (pintype "passive"))
    )
    (net (code "69") (name "Net-(R3.2C-2)") (class "Default")
      (node (ref "D3.3") (pin "C") (pinfunction "C_C") (pintype "passive"))
      (node (ref "R3.2") (pin "6") (pinfunction "2_6") (pintype "passive"))
    )
    (net (code "70") (name "Net-(R3.2D-2)") (class "Default")
      (node (ref "D3.4") (pin "C") (pinfunction "C_C") (pintype "passive"))
      (node (ref "R3.2") (pin "5") (pinfunction "2_5") (pintype "passive"))
    )
    (net (code "71") (name "Net-(R3.3A-2)") (class "Default")
      (node (ref "J3.2") (pin "1") (pinfunction "1_1") (pintype "passive"))
      (node (ref "J3.2") (pin "2") (pinfunction "2_2") (pintype "passive"))
      (node (ref "J3.2") (pin "3") (pinfunction "3_3") (pintype "passive"))
      (node (ref "J3.2") (pin "4") (pinfunction "4_4") (pintype "passive"))
      (node (ref "R3.3") (pin "8") (pinfunction "2_8") (pintype "passive"))
    )
    (net (code "72") (name "Net-(R3.3B-2)") (class "Default")
      (node (ref "J3.2") (pin "5") (pinfunction "5_5") (pintype "passive"))
      (node (ref "J3.2") (pin "6") (pinfunction "6_6") (pintype "passive"))
      (node (ref "J3.2") (pin "7") (pinfunction "7_7") (pintype "passive"))
      (node (ref "J3.2") (pin "8") (pinfunction "8_8") (pintype "passive"))
      (node (ref "R3.3") (pin "7") (pinfunction "2_7") (pintype "passive"))
    )
    (net (code "73") (name "Net-(R3.3C-2)") (class "Default")
      (node (ref "J3.2") (pin "10") (pinfunction "10_10") (pintype "passive"))
      (node (ref "J3.2") (pin "11") (pinfunction "11_11") (pintype "passive"))
      (node (ref "J3.2") (pin "12") (pinfunction "12_12") (pintype "passive"))
      (node (ref "J3.2") (pin "9") (pinfunction "9_9") (pintype "passive"))
      (node (ref "R3.3") (pin "6") (pinfunction "2_6") (pintype "passive"))
    )
    (net (code "74") (name "Net-(R3.3D-2)") (class "Default")
      (node (ref "J3.2") (pin "13") (pinfunction "13_13") (pintype "passive"))
      (node (ref "J3.2") (pin "14") (pinfunction "14_14") (pintype "passive"))
      (node (ref "J3.2") (pin "15") (pinfunction "15_15") (pintype "passive"))
      (node (ref "J3.2") (pin "16") (pinfunction "16_16") (pintype "passive"))
      (node (ref "R3.3") (pin "5") (pinfunction "2_5") (pintype "passive"))
    )
    (net (code "75") (name "Net-(R4.2A-2)") (class "Default")
      (node (ref "D4.1") (pin "C") (pinfunction "C_C") (pintype "passive"))
      (node (ref "R4.2") (pin "8") (pinfunction "2_8") (pintype "passive"))
    )
    (net (code "76") (name "Net-(R4.2B-2)") (class "Default")
      (node (ref "D4.2") (pin "C") (pinfunction "C_C") (pintype "passive"))
      (node (ref "R4.2") (pin "7") (pinfunction "2_7") (pintype "passive"))
    )
    (net (code "77") (name "Net-(R4.2C-2)") (class "Default")
      (node (ref "D4.3") (pin "C") (pinfunction "C_C") (pintype "passive"))
      (node (ref "R4.2") (pin "6") (pinfunction "2_6") (pintype "passive"))
    )
    (net (code "78") (name "Net-(R4.2D-2)") (class "Default")
      (node (ref "D4.4") (pin "C") (pinfunction "C_C") (pintype "passive"))
      (node (ref "R4.2") (pin "5") (pinfunction "2_5") (pintype "passive"))
    )
    (net (code "79") (name "Net-(R4.3A-2)") (class "Default")
      (node (ref "J4.2") (pin "1") (pinfunction "1_1") (pintype "passive"))
      (node (ref "J4.2") (pin "2") (pinfunction "2_2") (pintype "passive"))
      (node (ref "J4.2") (pin "3") (pinfunction "3_3") (pintype "passive"))
      (node (ref "J4.2") (pin "4") (pinfunction "4_4") (pintype "passive"))
      (node (ref "R4.3") (pin "8") (pinfunction "2_8") (pintype "passive"))
    )
    (net (code "80") (name "Net-(R4.3B-2)") (class "Default")
      (node (ref "J4.2") (pin "5") (pinfunction "5_5") (pintype "passive"))
      (node (ref "J4.2") (pin "6") (pinfunction "6_6") (pintype "passive"))
      (node (ref "J4.2") (pin "7") (pinfunction "7_7") (pintype "passive"))
      (node (ref "J4.2") (pin "8") (pinfunction "8_8") (pintype "passive"))
      (node (ref "R4.3") (pin "7") (pinfunction "2_7") (pintype "passive"))
    )
    (net (code "81") (name "Net-(R4.3C-2)") (class "Default")
      (node (ref "J4.2") (pin "10") (pinfunction "10_10") (pintype "passive"))
      (node (ref "J4.2") (pin "11") (pinfunction "11_11") (pintype "passive"))
      (node (ref "J4.2") (pin "12") (pinfunction "12_12") (pintype "passive"))
      (node (ref "J4.2") (pin "9") (pinfunction "9_9") (pintype "passive"))
      (node (ref "R4.3") (pin "6") (pinfunction "2_6") (pintype "passive"))
    )
    (net (code "82") (name "Net-(R4.3D-2)") (class "Default")
      (node (ref "J4.2") (pin "13") (pinfunction "13_13") (pintype "passive"))
      (node (ref "J4.2") (pin "14") (pinfunction "14_14") (pintype "passive"))
      (node (ref "J4.2") (pin "15") (pinfunction "15_15") (pintype "passive"))
      (node (ref "J4.2") (pin "16") (pinfunction "16_16") (pintype "passive"))
      (node (ref "R4.3") (pin "5") (pinfunction "2_5") (pintype "passive"))
    )
    (net (code "83") (name "Net-(RI.1B-1)") (class "Default")
      (node (ref "JI.1") (pin "5") (pinfunction "5_5") (pintype "passive"))
      (node (ref "JI.1") (pin "6") (pinfunction "6_6") (pintype "passive"))
      (node (ref "JI.1") (pin "7") (pinfunction "7_7") (pintype "passive"))
      (node (ref "JI.1") (pin "8") (pinfunction "8_8") (pintype "passive"))
      (node (ref "RI.1") (pin "2") (pinfunction "1_2") (pintype "passive"))
      (node (ref "SI.2") (pin "3") (pinfunction "B_3") (pintype "bidirectional"))
      (node (ref "SI.2") (pin "4") (pinfunction "B_4") (pintype "bidirectional"))
    )
    (net (code "84") (name "Net-(RI.1C-1)") (class "Default")
      (node (ref "JI.1") (pin "10") (pinfunction "10_10") (pintype "passive"))
      (node (ref "JI.1") (pin "11") (pinfunction "11_11") (pintype "passive"))
      (node (ref "JI.1") (pin "12") (pinfunction "12_12") (pintype "passive"))
      (node (ref "JI.1") (pin "9") (pinfunction "9_9") (pintype "passive"))
      (node (ref "RI.1") (pin "3") (pinfunction "1_3") (pintype "passive"))
      (node (ref "SI.3") (pin "3") (pinfunction "B_3") (pintype "bidirectional"))
      (node (ref "SI.3") (pin "4") (pinfunction "B_4") (pintype "bidirectional"))
    )
    (net (code "85") (name "Net-(RI.1D-1)") (class "Default")
      (node (ref "JI.1") (pin "13") (pinfunction "13_13") (pintype "passive"))
      (node (ref "JI.1") (pin "14") (pinfunction "14_14") (pintype "passive"))
      (node (ref "JI.1") (pin "15") (pinfunction "15_15") (pintype "passive"))
      (node (ref "JI.1") (pin "16") (pinfunction "16_16") (pintype "passive"))
      (node (ref "RI.1") (pin "4") (pinfunction "1_4") (pintype "passive"))
      (node (ref "SI.4") (pin "3") (pinfunction "B_3") (pintype "bidirectional"))
      (node (ref "SI.4") (pin "4") (pinfunction "B_4") (pintype "bidirectional"))
    )
    (net (code "86") (name "VCC") (class "Default")
      (node (ref "C1") (pin "1") (pinfunction "1_1") (pintype "passive"))
      (node (ref "C2") (pin "1") (pinfunction "1_1") (pintype "passive"))
      (node (ref "IC1") (pin "14") (pinfunction "VCC_14") (pintype "power_in"))
      (node (ref "IC2") (pin "14") (pinfunction "VCC_14") (pintype "power_in"))
      (node (ref "IC3") (pin "14") (pinfunction "VCC_14") (pintype "power_in"))
      (node (ref "J1.3") (pin "1") (pinfunction "1_1") (pintype "passive"))
      (node (ref "J1.3") (pin "2") (pinfunction "2_2") (pintype "passive"))
      (node (ref "J1.3") (pin "3") (pinfunction "3_3") (pintype "passive"))
      (node (ref "J1.3") (pin "4") (pinfunction "4_4") (pintype "passive"))
      (node (ref "J1.3") (pin "5") (pinfunction "5_5") (pintype "passive"))
      (node (ref "J1.3") (pin "6") (pinfunction "6_6") (pintype "passive"))
      (node (ref "J1.3") (pin "7") (pinfunction "7_7") (pintype "passive"))
      (node (ref "J1.3") (pin "8") (pinfunction "8_8") (pintype "passive"))
      (node (ref "J2.3") (pin "1") (pinfunction "1_1") (pintype "passive"))
      (node (ref "J2.3") (pin "2") (pinfunction "2_2") (pintype "passive"))
      (node (ref "J2.3") (pin "3") (pinfunction "3_3") (pintype "passive"))
      (node (ref "J2.3") (pin "4") (pinfunction "4_4") (pintype "passive"))
      (node (ref "J2.3") (pin "5") (pinfunction "5_5") (pintype "passive"))
      (node (ref "J2.3") (pin "6") (pinfunction "6_6") (pintype "passive"))
      (node (ref "J2.3") (pin "7") (pinfunction "7_7") (pintype "passive"))
      (node (ref "J2.3") (pin "8") (pinfunction "8_8") (pintype "passive"))
      (node (ref "J3.3") (pin "1") (pinfunction "1_1") (pintype "passive"))
      (node (ref "J3.3") (pin "2") (pinfunction "2_2") (pintype "passive"))
      (node (ref "J3.3") (pin "3") (pinfunction "3_3") (pintype "passive"))
      (node (ref "J3.3") (pin "4") (pinfunction "4_4") (pintype "passive"))
      (node (ref "J3.3") (pin "5") (pinfunction "5_5") (pintype "passive"))
      (node (ref "J3.3") (pin "6") (pinfunction "6_6") (pintype "passive"))
      (node (ref "J3.3") (pin "7") (pinfunction "7_7") (pintype "passive"))
      (node (ref "J3.3") (pin "8") (pinfunction "8_8") (pintype "passive"))
      (node (ref "J4.3") (pin "1") (pinfunction "1_1") (pintype "passive"))
      (node (ref "J4.3") (pin "2") (pinfunction "2_2") (pintype "passive"))
      (node (ref "J4.3") (pin "3") (pinfunction "3_3") (pintype "passive"))
      (node (ref "J4.3") (pin "4") (pinfunction "4_4") (pintype "passive"))
      (node (ref "J4.3") (pin "5") (pinfunction "5_5") (pintype "passive"))
      (node (ref "J4.3") (pin "6") (pinfunction "6_6") (pintype "passive"))
      (node (ref "J4.3") (pin "7") (pinfunction "7_7") (pintype "passive"))
      (node (ref "J4.3") (pin "8") (pinfunction "8_8") (pintype "passive"))
      (node (ref "NAND4") (pin "14") (pinfunction "VCC_14") (pintype "power_in"))
      (node (ref "PWR") (pin "1") (pinfunction "1_1") (pintype "passive"))
      (node (ref "SI.1") (pin "1") (pinfunction "A_1") (pintype "bidirectional"))
      (node (ref "SI.1") (pin "2") (pinfunction "A_2") (pintype "bidirectional"))
      (node (ref "SI.2") (pin "1") (pinfunction "A_1") (pintype "bidirectional"))
      (node (ref "SI.2") (pin "2") (pinfunction "A_2") (pintype "bidirectional"))
      (node (ref "SI.3") (pin "1") (pinfunction "A_1") (pintype "bidirectional"))
      (node (ref "SI.3") (pin "2") (pinfunction "A_2") (pintype "bidirectional"))
      (node (ref "SI.4") (pin "1") (pinfunction "A_1") (pintype "bidirectional"))
      (node (ref "SI.4") (pin "2") (pinfunction "A_2") (pintype "bidirectional"))
      (node (ref "USB") (pin "1") (pinfunction "VCC_1") (pintype "bidirectional"))
    )
    (net (code "87") (name "unconnected-(USB-D+-Pad3)") (class "Default")
      (node (ref "USB") (pin "3") (pinfunction "D+_3") (pintype "bidirectional"))
    )
    (net (code "88") (name "unconnected-(USB-D--Pad2)") (class "Default")
      (node (ref "USB") (pin "2") (pinfunction "D-_2") (pintype "bidirectional"))
    )
    (net (code "89") (name "unconnected-(USB-ID-Pad4)") (class "Default")
      (node (ref "USB") (pin "4") (pinfunction "ID_4") (pintype "bidirectional"))
    )
  )
)
